# Modular_RFPA_v101.net
KiCad netlist of a schematic drawn in EAGLE
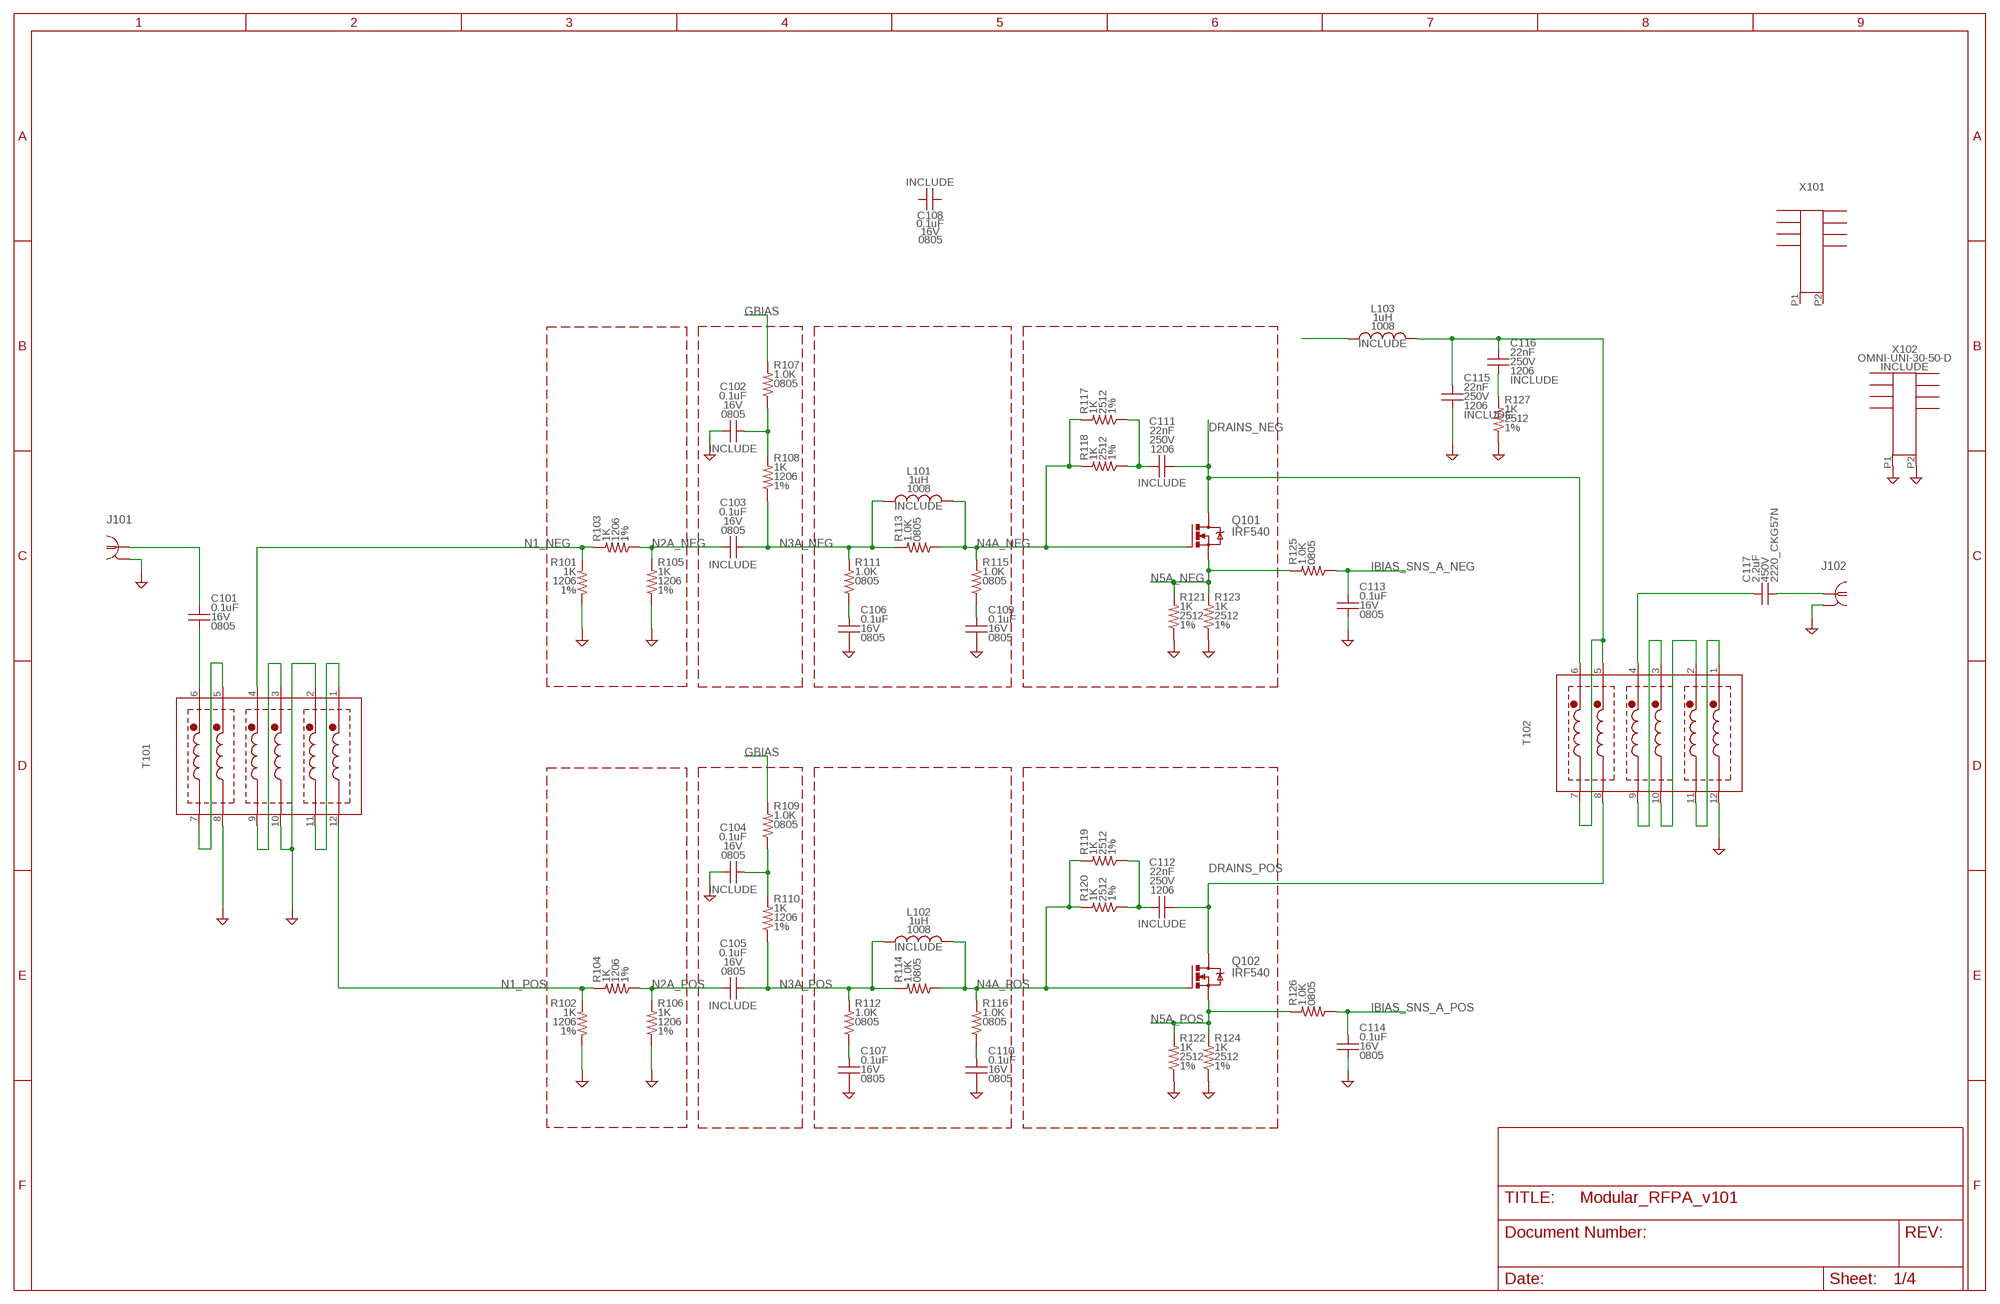
[diagram p0: schematic, sheet 1]
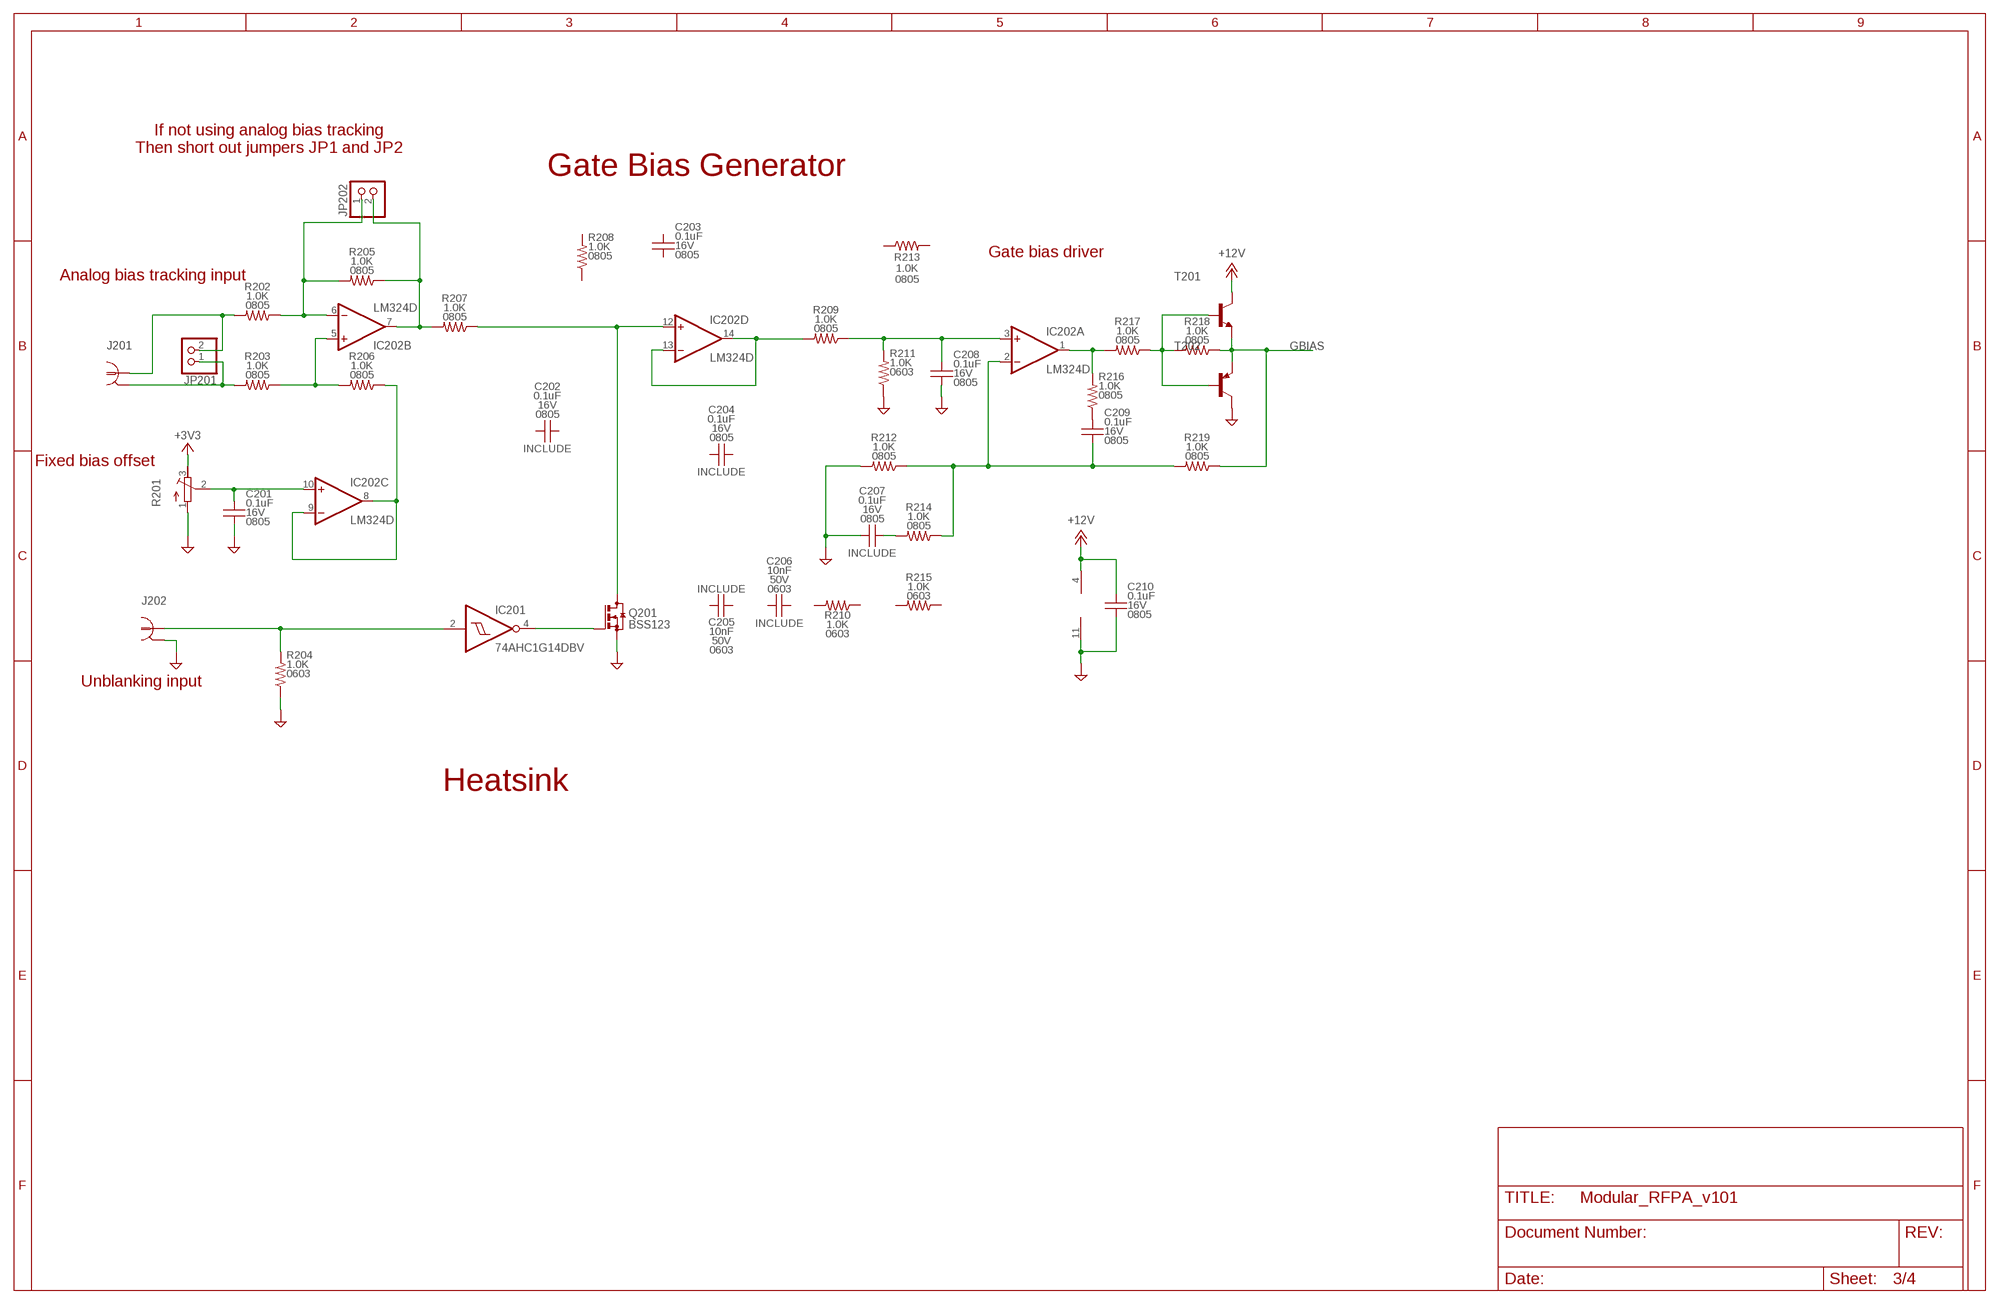
[diagram p1: schematic, sheet 3]
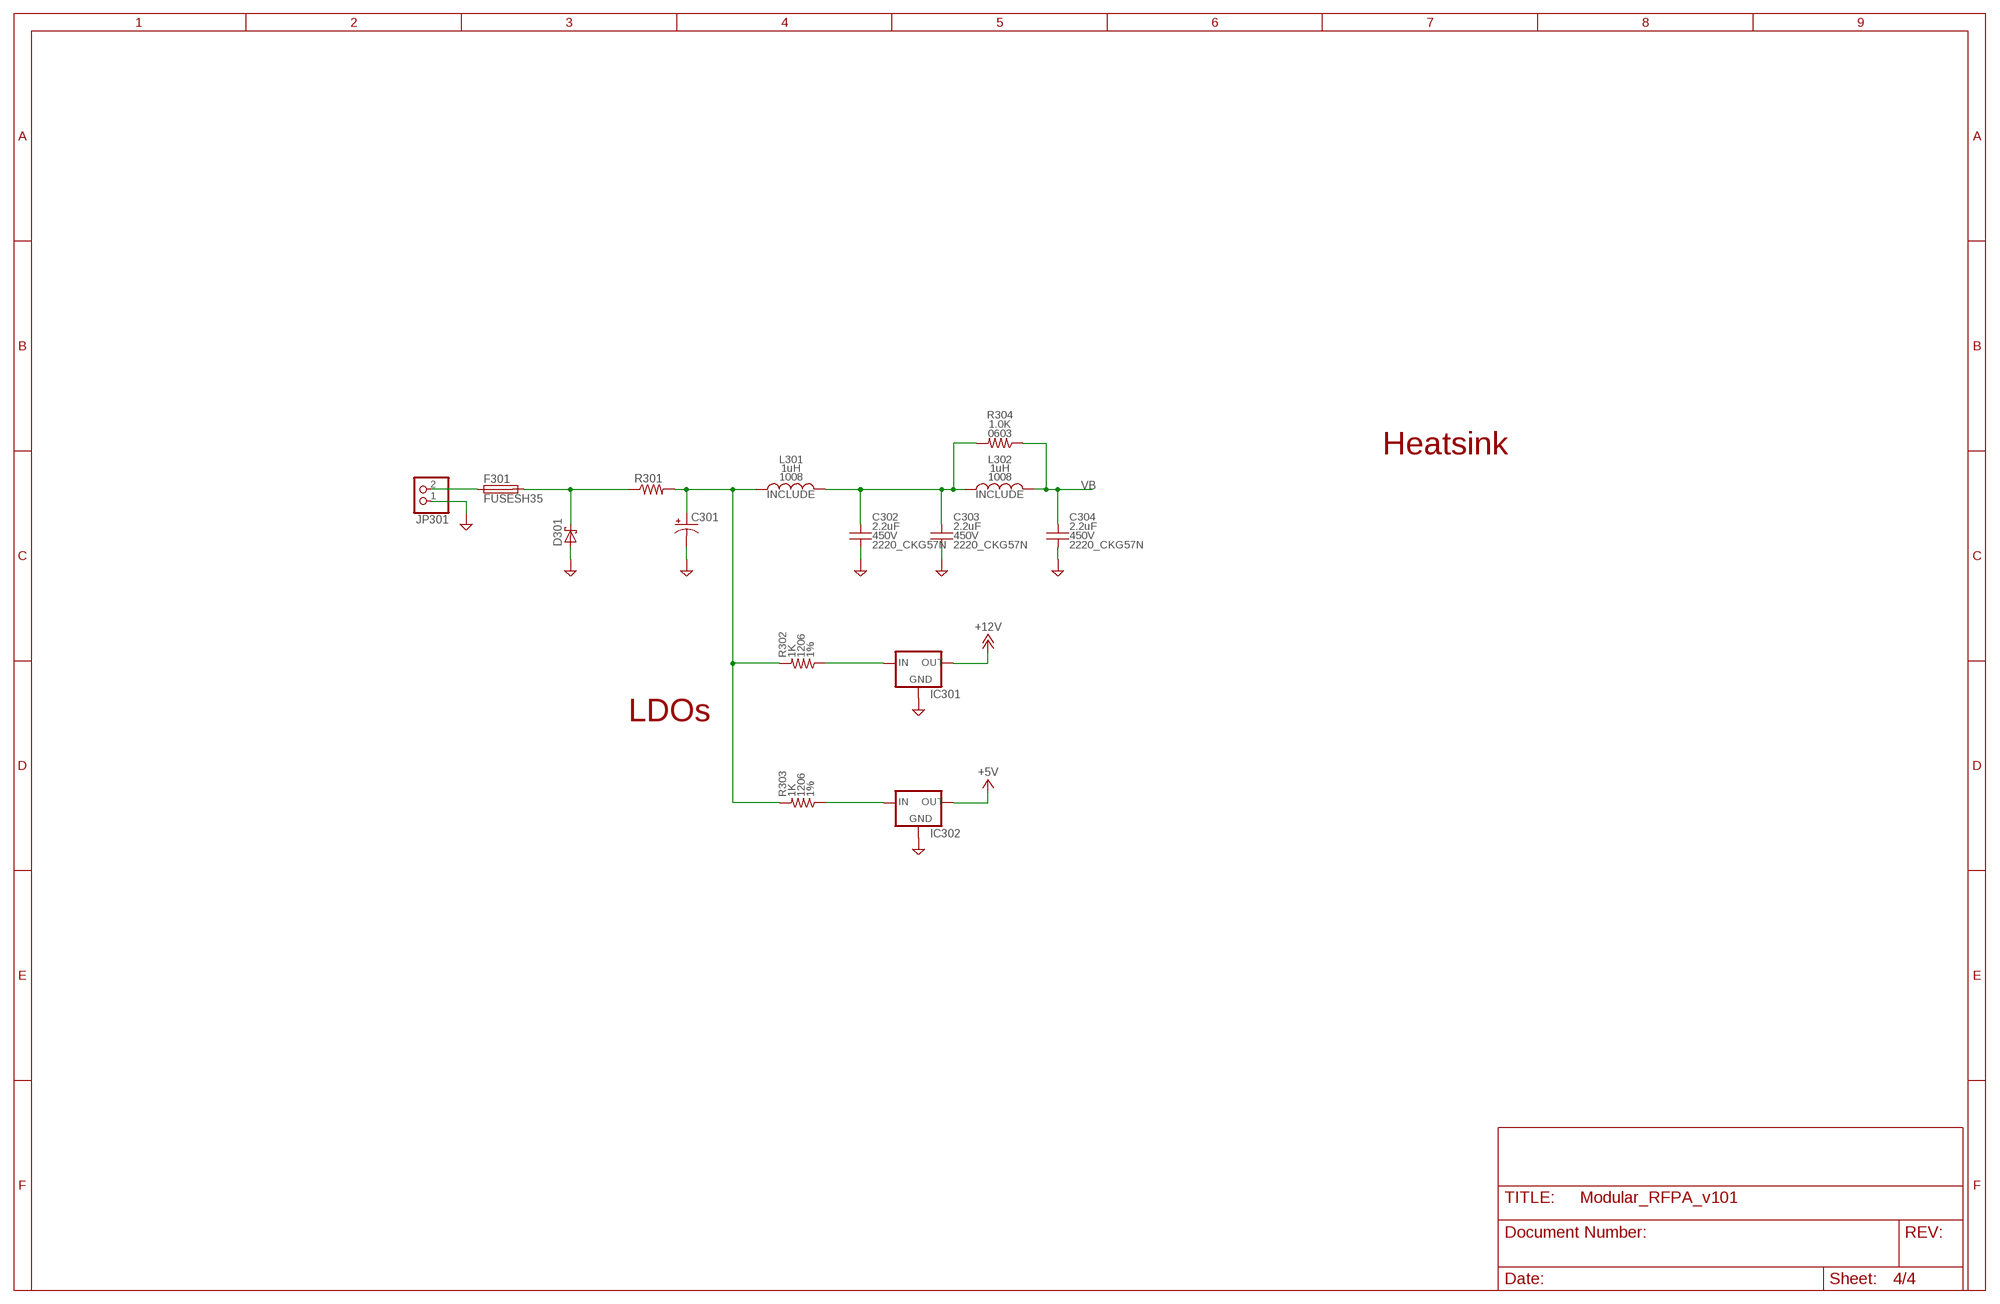
[diagram p2: schematic, sheet 4]

(export (version "E")
  (design (tool "Eeschema 10.0.6"))
  (components
    (comp (ref "C201")
      (value "0.1uF")
      (footprint "eagle-import:0805_IPC-7351B")
      (fields (field (name "VOLTAGE") "16V"))
      (libsource (lib "eagle-import") (part "C0805_IPCC-0.1U-16V-0805-X7R"))
    )
    (comp (ref "C202")
      (value "0.1uF")
      (footprint "eagle-import:0805_IPC-7351B")
      (fields (field (name "PACKAGE") "0805") (field (name "VOLTAGE") "16V") (field (name "BOM") "INCLUDE"))
      (libsource (lib "eagle-import") (part "C0805_IPCC-0.1U-16V-0805-X7R"))
    )
    (comp (ref "C203")
      (value "0.1uF")
      (footprint "eagle-import:0805_IPC-7351B")
      (fields (field (name "VOLTAGE") "16V"))
      (libsource (lib "eagle-import") (part "C0805_IPCC-0.1U-16V-0805-X7R"))
    )
    (comp (ref "C204")
      (value "0.1uF")
      (footprint "eagle-import:0805_IPC-7351B")
      (fields (field (name "PACKAGE") "0805") (field (name "VOLTAGE") "16V") (field (name "BOM") "INCLUDE"))
      (libsource (lib "eagle-import") (part "C0805_IPCC-0.1U-16V-0805-X7R"))
    )
    (comp (ref "C205")
      (value "10nF")
      (footprint "eagle-import:0603_IPC-7351B")
      (fields
        (field (name "BOM") "INCLUDE")
        (field (name "PACKAGE") "0603")
        (field (name "PARTNO") "C1608C0G1H103J080AA")
        (field (name "VOLTAGE") "50V")
      )
      (libsource (lib "eagle-import") (part "C0603_IPCC-10N-50V-0603-NP0"))
    )
    (comp (ref "C206")
      (value "10nF")
      (footprint "eagle-import:0603_IPC-7351B")
      (fields
        (field (name "BOM") "INCLUDE")
        (field (name "PACKAGE") "0603")
        (field (name "PARTNO") "C1608C0G1H103J080AA")
        (field (name "VOLTAGE") "50V")
      )
      (libsource (lib "eagle-import") (part "C0603_IPCC-10N-50V-0603-NP0"))
    )
    (comp (ref "C207")
      (value "0.1uF")
      (footprint "eagle-import:0805_IPC-7351B")
      (fields (field (name "PACKAGE") "0805") (field (name "VOLTAGE") "16V") (field (name "BOM") "INCLUDE"))
      (libsource (lib "eagle-import") (part "C0805_IPCC-0.1U-16V-0805-X7R"))
    )
    (comp (ref "C208")
      (value "0.1uF")
      (footprint "eagle-import:0805_IPC-7351B")
      (fields (field (name "VOLTAGE") "16V"))
      (libsource (lib "eagle-import") (part "C0805_IPCC-0.1U-16V-0805-X7R"))
    )
    (comp (ref "C209")
      (value "0.1uF")
      (footprint "eagle-import:0805_IPC-7351B")
      (fields (field (name "VOLTAGE") "16V"))
      (libsource (lib "eagle-import") (part "C0805_IPCC-0.1U-16V-0805-X7R"))
    )
    (comp (ref "C210")
      (value "0.1uF")
      (footprint "eagle-import:0805_IPC-7351B")
      (fields (field (name "VOLTAGE") "16V"))
      (libsource (lib "eagle-import") (part "C0805_IPCC-0.1U-16V-0805-X7R"))
    )
    (comp (ref "IC201")
      (value "74AHC1G14DBV")
      (footprint "eagle-import:SOT23-5")
      (libsource (lib "eagle-import") (part "741G14DBVAHC"))
    )
    (comp (ref "IC202")
      (value "LM324D")
      (footprint "eagle-import:SO14")
      (libsource (lib "eagle-import") (part "LM324D"))
    )
    (comp (ref "J201")
      (value "COAXBNC_EDGE")
      (footprint "eagle-import:BNC_EDGE")
      (libsource (lib "eagle-import") (part "COAXBNC_EDGE"))
    )
    (comp (ref "J202")
      (value "COAXBNC_EDGE")
      (footprint "eagle-import:BNC_EDGE")
      (libsource (lib "eagle-import") (part "COAXBNC_EDGE"))
    )
    (comp (ref "JP201")
      (value "PINHD-1X2")
      (footprint "eagle-import:1X02")
      (libsource (lib "eagle-import") (part "PINHD-1X2"))
    )
    (comp (ref "JP202")
      (value "PINHD-1X2")
      (footprint "eagle-import:1X02")
      (libsource (lib "eagle-import") (part "PINHD-1X2"))
    )
    (comp (ref "Q201")
      (value "BSS123")
      (footprint "eagle-import:SOT23")
      (libsource (lib "eagle-import") (part "BSS123"))
    )
    (comp (ref "R201")
      (value "R-TRIMM3299W")
      (footprint "eagle-import:RTRIM3299W")
      (libsource (lib "eagle-import") (part "R-TRIMM3299W"))
    )
    (comp (ref "R202")
      (value "1.0K")
      (footprint "eagle-import:0805_IPC-7351B")
      (fields (field (name "PACKAGE") "0805"))
      (libsource (lib "eagle-import") (part "R0805_IPCR-1.0K-0.1%-0805-0.1W"))
    )
    (comp (ref "R203")
      (value "1.0K")
      (footprint "eagle-import:0805_IPC-7351B")
      (fields (field (name "PACKAGE") "0805"))
      (libsource (lib "eagle-import") (part "R0805_IPCR-1.0K-0.1%-0805-0.1W"))
    )
    (comp (ref "R204")
      (value "1.0K")
      (footprint "eagle-import:0603_IPC-7351B")
      (libsource (lib "eagle-import") (part "R0603_IPCR-1.0K-0.1%-0603-0.1W"))
    )
    (comp (ref "R205")
      (value "1.0K")
      (footprint "eagle-import:0805_IPC-7351B")
      (fields (field (name "PACKAGE") "0805"))
      (libsource (lib "eagle-import") (part "R0805_IPCR-1.0K-0.1%-0805-0.1W"))
    )
    (comp (ref "R206")
      (value "1.0K")
      (footprint "eagle-import:0805_IPC-7351B")
      (fields (field (name "PACKAGE") "0805"))
      (libsource (lib "eagle-import") (part "R0805_IPCR-1.0K-0.1%-0805-0.1W"))
    )
    (comp (ref "R207")
      (value "1.0K")
      (footprint "eagle-import:0805_IPC-7351B")
      (fields (field (name "PACKAGE") "0805"))
      (libsource (lib "eagle-import") (part "R0805_IPCR-1.0K-0.1%-0805-0.1W"))
    )
    (comp (ref "R208")
      (value "1.0K")
      (footprint "eagle-import:0805_IPC-7351B")
      (libsource (lib "eagle-import") (part "R0805_IPCR-1.0K-0.1%-0805-0.1W"))
    )
    (comp (ref "R209")
      (value "1.0K")
      (footprint "eagle-import:0805_IPC-7351B")
      (fields (field (name "PACKAGE") "0805"))
      (libsource (lib "eagle-import") (part "R0805_IPCR-1.0K-0.1%-0805-0.1W"))
    )
    (comp (ref "R210")
      (value "1.0K")
      (footprint "eagle-import:0603_IPC-7351B")
      (fields (field (name "PACKAGE") "0603"))
      (libsource (lib "eagle-import") (part "R0603_IPCR-1.0K-0.1%-0603-0.1W"))
    )
    (comp (ref "R211")
      (value "1.0K")
      (footprint "eagle-import:0603_IPC-7351B")
      (libsource (lib "eagle-import") (part "R0603_IPCR-1.0K-0.1%-0603-0.1W"))
    )
    (comp (ref "R212")
      (value "1.0K")
      (footprint "eagle-import:0805_IPC-7351B")
      (fields (field (name "PACKAGE") "0805"))
      (libsource (lib "eagle-import") (part "R0805_IPCR-1.0K-0.1%-0805-0.1W"))
    )
    (comp (ref "R213")
      (value "1.0K")
      (footprint "eagle-import:0805_IPC-7351B")
      (fields (field (name "PACKAGE") "0805"))
      (libsource (lib "eagle-import") (part "R0805_IPCR-1.0K-0.1%-0805-0.1W"))
    )
    (comp (ref "R214")
      (value "1.0K")
      (footprint "eagle-import:0805_IPC-7351B")
      (fields (field (name "PACKAGE") "0805"))
      (libsource (lib "eagle-import") (part "R0805_IPCR-1.0K-0.1%-0805-0.1W"))
    )
    (comp (ref "R215")
      (value "1.0K")
      (footprint "eagle-import:0603_IPC-7351B")
      (fields (field (name "PACKAGE") "0603"))
      (libsource (lib "eagle-import") (part "R0603_IPCR-1.0K-0.1%-0603-0.1W"))
    )
    (comp (ref "R216")
      (value "1.0K")
      (footprint "eagle-import:0805_IPC-7351B")
      (libsource (lib "eagle-import") (part "R0805_IPCR-1.0K-0.1%-0805-0.1W"))
    )
    (comp (ref "R217")
      (value "1.0K")
      (footprint "eagle-import:0805_IPC-7351B")
      (fields (field (name "PACKAGE") "0805"))
      (libsource (lib "eagle-import") (part "R0805_IPCR-1.0K-0.1%-0805-0.1W"))
    )
    (comp (ref "R218")
      (value "1.0K")
      (footprint "eagle-import:0805_IPC-7351B")
      (fields (field (name "PACKAGE") "0805"))
      (libsource (lib "eagle-import") (part "R0805_IPCR-1.0K-0.1%-0805-0.1W"))
    )
    (comp (ref "R219")
      (value "1.0K")
      (footprint "eagle-import:0805_IPC-7351B")
      (fields (field (name "PACKAGE") "0805"))
      (libsource (lib "eagle-import") (part "R0805_IPCR-1.0K-0.1%-0805-0.1W"))
    )
    (comp (ref "T201")
      (value "BC808-NPN-SOT23-BEC")
      (footprint "eagle-import:SOT23-BEC")
      (libsource (lib "eagle-import") (part "-NPN-SOT23-BECBC808"))
    )
    (comp (ref "T202")
      (value "BC807-16-PNP-SOT23-BEC")
      (footprint "eagle-import:SOT23-BEC")
      (libsource (lib "eagle-import") (part "-PNP-SOT23-BECBC807-16"))
    )
    (comp (ref "C301")
      (value "CPOL-USE10-25")
      (footprint "eagle-import:EB25D")
      (libsource (lib "eagle-import") (part "CPOL-USE10-25"))
    )
    (comp (ref "C302")
      (value "2.2uF")
      (footprint "eagle-import:C2220_CKG57N")
      (fields (field (name "PARTNO") "CKG57NX7T2W225M500JJ") (field (name "VOLTAGE") "450V"))
      (libsource (lib "eagle-import") (part "CC2220_CKG57NC-2.2U-450V-20%-2220-X7T"))
    )
    (comp (ref "C303")
      (value "2.2uF")
      (footprint "eagle-import:C2220_CKG57N")
      (fields (field (name "PARTNO") "CKG57NX7T2W225M500JJ") (field (name "VOLTAGE") "450V"))
      (libsource (lib "eagle-import") (part "CC2220_CKG57NC-2.2U-450V-20%-2220-X7T"))
    )
    (comp (ref "C304")
      (value "2.2uF")
      (footprint "eagle-import:C2220_CKG57N")
      (fields (field (name "PARTNO") "CKG57NX7T2W225M500JJ") (field (name "VOLTAGE") "450V"))
      (libsource (lib "eagle-import") (part "CC2220_CKG57NC-2.2U-450V-20%-2220-X7T"))
    )
    (comp (ref "D301")
      (value "SCHOTTKY-DIODESMC")
      (footprint "eagle-import:SMC")
      (libsource (lib "eagle-import") (part "SCHOTTKY-DIODESMC"))
    )
    (comp (ref "F301")
      (value "FUSESH35")
      (footprint "eagle-import:SH25")
      (libsource (lib "eagle-import") (part "FUSESH35"))
    )
    (comp (ref "IC301")
      (value "78XXS")
      (footprint "eagle-import:78XXS")
      (libsource (lib "eagle-import") (part "78XXS"))
    )
    (comp (ref "IC302")
      (value "78XXS")
      (footprint "eagle-import:78XXS")
      (libsource (lib "eagle-import") (part "78XXS"))
    )
    (comp (ref "JP301")
      (value "PINHD-1X2")
      (footprint "eagle-import:1X02")
      (libsource (lib "eagle-import") (part "PINHD-1X2"))
    )
    (comp (ref "L301")
      (value "1uH")
      (footprint "eagle-import:L1008")
      (fields (field (name "PARTNO") "1008CS-102XJEC"))
      (libsource (lib "eagle-import") (part "L_CHIP1008L-1.0U-AIR-5%-1008-0.37A"))
    )
    (comp (ref "L302")
      (value "1uH")
      (footprint "eagle-import:L1008")
      (fields (field (name "PARTNO") "1008CS-102XJEC"))
      (libsource (lib "eagle-import") (part "L_CHIP1008L-1.0U-AIR-5%-1008-0.37A"))
    )
    (comp (ref "R301")
      (value "R-US_0617/22")
      (footprint "eagle-import:0617_22")
      (libsource (lib "eagle-import") (part "R-US_0617/22"))
    )
    (comp (ref "R302")
      (value "1K")
      (footprint "eagle-import:R1206")
      (fields (field (name "POWER") "0.25"))
      (libsource (lib "eagle-import") (part "RR1206R-1.0K-1%-1206-0.25W"))
    )
    (comp (ref "R303")
      (value "1K")
      (footprint "eagle-import:R1206")
      (fields (field (name "POWER") "0.25"))
      (libsource (lib "eagle-import") (part "RR1206R-1.0K-1%-1206-0.25W"))
    )
    (comp (ref "R304")
      (value "1.0K")
      (footprint "eagle-import:0603_IPC-7351B")
      (fields (field (name "PACKAGE") "0603"))
      (libsource (lib "eagle-import") (part "R0603_IPCR-1.0K-0.1%-0603-0.1W"))
    )
    (comp (ref "C101")
      (value "0.1uF")
      (footprint "eagle-import:0805_IPC-7351B")
      (fields (field (name "VOLTAGE") "16V"))
      (libsource (lib "eagle-import") (part "C0805_IPCC-0.1U-16V-0805-X7R"))
    )
    (comp (ref "C102")
      (value "0.1uF")
      (footprint "eagle-import:0805_IPC-7351B")
      (fields (field (name "PACKAGE") "0805") (field (name "VOLTAGE") "16V") (field (name "BOM") "INCLUDE"))
      (libsource (lib "eagle-import") (part "C0805_IPCC-0.1U-16V-0805-X7R"))
    )
    (comp (ref "C103")
      (value "0.1uF")
      (footprint "eagle-import:0805_IPC-7351B")
      (fields (field (name "PACKAGE") "0805") (field (name "VOLTAGE") "16V") (field (name "BOM") "INCLUDE"))
      (libsource (lib "eagle-import") (part "C0805_IPCC-0.1U-16V-0805-X7R"))
    )
    (comp (ref "C104")
      (value "0.1uF")
      (footprint "eagle-import:0805_IPC-7351B")
      (fields (field (name "PACKAGE") "0805") (field (name "VOLTAGE") "16V") (field (name "BOM") "INCLUDE"))
      (libsource (lib "eagle-import") (part "C0805_IPCC-0.1U-16V-0805-X7R"))
    )
    (comp (ref "C105")
      (value "0.1uF")
      (footprint "eagle-import:0805_IPC-7351B")
      (fields (field (name "PACKAGE") "0805") (field (name "VOLTAGE") "16V") (field (name "BOM") "INCLUDE"))
      (libsource (lib "eagle-import") (part "C0805_IPCC-0.1U-16V-0805-X7R"))
    )
    (comp (ref "C106")
      (value "0.1uF")
      (footprint "eagle-import:0805_IPC-7351B")
      (fields (field (name "VOLTAGE") "16V"))
      (libsource (lib "eagle-import") (part "C0805_IPCC-0.1U-16V-0805-X7R"))
    )
    (comp (ref "C107")
      (value "0.1uF")
      (footprint "eagle-import:0805_IPC-7351B")
      (fields (field (name "VOLTAGE") "16V"))
      (libsource (lib "eagle-import") (part "C0805_IPCC-0.1U-16V-0805-X7R"))
    )
    (comp (ref "C108")
      (value "0.1uF")
      (footprint "eagle-import:0805_IPC-7351B")
      (fields (field (name "PACKAGE") "0805") (field (name "VOLTAGE") "16V") (field (name "BOM") "INCLUDE"))
      (libsource (lib "eagle-import") (part "C0805_IPCC-0.1U-16V-0805-X7R"))
    )
    (comp (ref "C109")
      (value "0.1uF")
      (footprint "eagle-import:0805_IPC-7351B")
      (fields (field (name "VOLTAGE") "16V"))
      (libsource (lib "eagle-import") (part "C0805_IPCC-0.1U-16V-0805-X7R"))
    )
    (comp (ref "C110")
      (value "0.1uF")
      (footprint "eagle-import:0805_IPC-7351B")
      (fields (field (name "VOLTAGE") "16V"))
      (libsource (lib "eagle-import") (part "C0805_IPCC-0.1U-16V-0805-X7R"))
    )
    (comp (ref "C111")
      (value "22nF")
      (footprint "eagle-import:C1206")
      (fields
        (field (name "BOM") "INCLUDE")
        (field (name "PACKAGE") "1206")
        (field (name "PARTNO") "C3216NP02E223J160AA")
        (field (name "VOLTAGE") "250V")
      )
      (libsource (lib "eagle-import") (part "CC1206C-22N-250V-5%-1206-NP0"))
    )
    (comp (ref "C112")
      (value "22nF")
      (footprint "eagle-import:C1206")
      (fields
        (field (name "BOM") "INCLUDE")
        (field (name "PACKAGE") "1206")
        (field (name "PARTNO") "C3216NP02E223J160AA")
        (field (name "VOLTAGE") "250V")
      )
      (libsource (lib "eagle-import") (part "CC1206C-22N-250V-5%-1206-NP0"))
    )
    (comp (ref "C113")
      (value "0.1uF")
      (footprint "eagle-import:0805_IPC-7351B")
      (fields (field (name "VOLTAGE") "16V"))
      (libsource (lib "eagle-import") (part "C0805_IPCC-0.1U-16V-0805-X7R"))
    )
    (comp (ref "C114")
      (value "0.1uF")
      (footprint "eagle-import:0805_IPC-7351B")
      (fields (field (name "VOLTAGE") "16V"))
      (libsource (lib "eagle-import") (part "C0805_IPCC-0.1U-16V-0805-X7R"))
    )
    (comp (ref "C115")
      (value "22nF")
      (footprint "eagle-import:C1206")
      (fields (field (name "PARTNO") "C3216NP02E223J160AA") (field (name "VOLTAGE") "250V"))
      (libsource (lib "eagle-import") (part "CC1206C-22N-250V-5%-1206-NP0"))
    )
    (comp (ref "C116")
      (value "22nF")
      (footprint "eagle-import:C1206")
      (fields (field (name "PARTNO") "C3216NP02E223J160AA") (field (name "VOLTAGE") "250V"))
      (libsource (lib "eagle-import") (part "CC1206C-22N-250V-5%-1206-NP0"))
    )
    (comp (ref "C117")
      (value "2.2uF")
      (footprint "eagle-import:C2220_CKG57N")
      (fields (field (name "PARTNO") "CKG57NX7T2W225M500JJ") (field (name "VOLTAGE") "450V"))
      (libsource (lib "eagle-import") (part "CC2220_CKG57NC-2.2U-450V-20%-2220-X7T"))
    )
    (comp (ref "J101")
      (value "COAXBNC_EDGE")
      (footprint "eagle-import:BNC_EDGE")
      (libsource (lib "eagle-import") (part "COAXBNC_EDGE"))
    )
    (comp (ref "J102")
      (value "COAXBNC_EDGE")
      (footprint "eagle-import:BNC_EDGE")
      (libsource (lib "eagle-import") (part "COAXBNC_EDGE"))
    )
    (comp (ref "L101")
      (value "1uH")
      (footprint "eagle-import:L1008")
      (fields (field (name "PARTNO") "1008CS-102XJEC"))
      (libsource (lib "eagle-import") (part "L_CHIP1008L-1.0U-AIR-5%-1008-0.37A"))
    )
    (comp (ref "L102")
      (value "1uH")
      (footprint "eagle-import:L1008")
      (fields (field (name "PARTNO") "1008CS-102XJEC"))
      (libsource (lib "eagle-import") (part "L_CHIP1008L-1.0U-AIR-5%-1008-0.37A"))
    )
    (comp (ref "L103")
      (value "1uH")
      (footprint "eagle-import:L1008")
      (fields (field (name "PARTNO") "1008CS-102XJEC"))
      (libsource (lib "eagle-import") (part "L_CHIP1008L-1.0U-AIR-5%-1008-0.37A"))
    )
    (comp (ref "Q101")
      (value "IRF540")
      (footprint "eagle-import:TO220BV")
      (libsource (lib "eagle-import") (part "IRF540"))
    )
    (comp (ref "Q102")
      (value "IRF540")
      (footprint "eagle-import:TO220BV")
      (libsource (lib "eagle-import") (part "IRF540"))
    )
    (comp (ref "R101")
      (value "1K")
      (footprint "eagle-import:R1206")
      (fields (field (name "POWER") "0.25"))
      (libsource (lib "eagle-import") (part "RR1206R-1.0K-1%-1206-0.25W"))
    )
    (comp (ref "R102")
      (value "1K")
      (footprint "eagle-import:R1206")
      (fields (field (name "POWER") "0.25"))
      (libsource (lib "eagle-import") (part "RR1206R-1.0K-1%-1206-0.25W"))
    )
    (comp (ref "R103")
      (value "1K")
      (footprint "eagle-import:R1206")
      (fields (field (name "POWER") "0.25"))
      (libsource (lib "eagle-import") (part "RR1206R-1.0K-1%-1206-0.25W"))
    )
    (comp (ref "R104")
      (value "1K")
      (footprint "eagle-import:R1206")
      (fields (field (name "POWER") "0.25"))
      (libsource (lib "eagle-import") (part "RR1206R-1.0K-1%-1206-0.25W"))
    )
    (comp (ref "R105")
      (value "1K")
      (footprint "eagle-import:R1206")
      (fields (field (name "POWER") "0.25"))
      (libsource (lib "eagle-import") (part "RR1206R-1.0K-1%-1206-0.25W"))
    )
    (comp (ref "R106")
      (value "1K")
      (footprint "eagle-import:R1206")
      (fields (field (name "POWER") "0.25"))
      (libsource (lib "eagle-import") (part "RR1206R-1.0K-1%-1206-0.25W"))
    )
    (comp (ref "R107")
      (value "1.0K")
      (footprint "eagle-import:0805_IPC-7351B")
      (libsource (lib "eagle-import") (part "R0805_IPCR-1.0K-0.1%-0805-0.1W"))
    )
    (comp (ref "R108")
      (value "1K")
      (footprint "eagle-import:R1206")
      (fields (field (name "POWER") "0.25"))
      (libsource (lib "eagle-import") (part "RR1206R-1.0K-1%-1206-0.25W"))
    )
    (comp (ref "R109")
      (value "1.0K")
      (footprint "eagle-import:0805_IPC-7351B")
      (libsource (lib "eagle-import") (part "R0805_IPCR-1.0K-0.1%-0805-0.1W"))
    )
    (comp (ref "R110")
      (value "1K")
      (footprint "eagle-import:R1206")
      (fields (field (name "POWER") "0.25"))
      (libsource (lib "eagle-import") (part "RR1206R-1.0K-1%-1206-0.25W"))
    )
    (comp (ref "R111")
      (value "1.0K")
      (footprint "eagle-import:0805_IPC-7351B")
      (libsource (lib "eagle-import") (part "R0805_IPCR-1.0K-0.1%-0805-0.1W"))
    )
    (comp (ref "R112")
      (value "1.0K")
      (footprint "eagle-import:0805_IPC-7351B")
      (libsource (lib "eagle-import") (part "R0805_IPCR-1.0K-0.1%-0805-0.1W"))
    )
    (comp (ref "R113")
      (value "1.0K")
      (footprint "eagle-import:0805_IPC-7351B")
      (libsource (lib "eagle-import") (part "R0805_IPCR-1.0K-0.1%-0805-0.1W"))
    )
    (comp (ref "R114")
      (value "1.0K")
      (footprint "eagle-import:0805_IPC-7351B")
      (libsource (lib "eagle-import") (part "R0805_IPCR-1.0K-0.1%-0805-0.1W"))
    )
    (comp (ref "R115")
      (value "1.0K")
      (footprint "eagle-import:0805_IPC-7351B")
      (libsource (lib "eagle-import") (part "R0805_IPCR-1.0K-0.1%-0805-0.1W"))
    )
    (comp (ref "R116")
      (value "1.0K")
      (footprint "eagle-import:0805_IPC-7351B")
      (libsource (lib "eagle-import") (part "R0805_IPCR-1.0K-0.1%-0805-0.1W"))
    )
    (comp (ref "R117")
      (value "1K")
      (footprint "eagle-import:R2512")
      (fields (field (name "POWER") "1"))
      (libsource (lib "eagle-import") (part "RR2512R-1K-1%-2512-1W"))
    )
    (comp (ref "R118")
      (value "1K")
      (footprint "eagle-import:R2512")
      (fields (field (name "POWER") "1"))
      (libsource (lib "eagle-import") (part "RR2512R-1K-1%-2512-1W"))
    )
    (comp (ref "R119")
      (value "1K")
      (footprint "eagle-import:R2512")
      (fields (field (name "POWER") "1"))
      (libsource (lib "eagle-import") (part "RR2512R-1K-1%-2512-1W"))
    )
    (comp (ref "R120")
      (value "1K")
      (footprint "eagle-import:R2512")
      (fields (field (name "POWER") "1"))
      (libsource (lib "eagle-import") (part "RR2512R-1K-1%-2512-1W"))
    )
    (comp (ref "R121")
      (value "1K")
      (footprint "eagle-import:R2512")
      (fields (field (name "POWER") "1"))
      (libsource (lib "eagle-import") (part "RR2512R-1K-1%-2512-1W"))
    )
    (comp (ref "R122")
      (value "1K")
      (footprint "eagle-import:R2512")
      (fields (field (name "POWER") "1"))
      (libsource (lib "eagle-import") (part "RR2512R-1K-1%-2512-1W"))
    )
    (comp (ref "R123")
      (value "1K")
      (footprint "eagle-import:R2512")
      (fields (field (name "POWER") "1"))
      (libsource (lib "eagle-import") (part "RR2512R-1K-1%-2512-1W"))
    )
    (comp (ref "R124")
      (value "1K")
      (footprint "eagle-import:R2512")
      (fields (field (name "POWER") "1"))
      (libsource (lib "eagle-import") (part "RR2512R-1K-1%-2512-1W"))
    )
    (comp (ref "R125")
      (value "1.0K")
      (footprint "eagle-import:0805_IPC-7351B")
      (libsource (lib "eagle-import") (part "R0805_IPCR-1.0K-0.1%-0805-0.1W"))
    )
    (comp (ref "R126")
      (value "1.0K")
      (footprint "eagle-import:0805_IPC-7351B")
      (libsource (lib "eagle-import") (part "R0805_IPCR-1.0K-0.1%-0805-0.1W"))
    )
    (comp (ref "R127")
      (value "1K")
      (footprint "eagle-import:R2512")
      (fields (field (name "POWER") "1"))
      (libsource (lib "eagle-import") (part "RR2512R-1K-1%-2512-1W"))
    )
    (comp (ref "T101")
      (value "HP5_TRAFOHP5")
      (footprint "eagle-import:HP5")
      (libsource (lib "eagle-import") (part "HP5_TRAFOHP5"))
    )
    (comp (ref "T102")
      (value "HP5_TRAFOHP5")
      (footprint "eagle-import:HP5")
      (libsource (lib "eagle-import") (part "HP5_TRAFOHP5"))
    )
    (comp (ref "X101")
      (value "HEATSINK_OMNI_DUAL30-75-D")
      (footprint "eagle-import:OMNI-UNI-30-75-D")
      (libsource (lib "eagle-import") (part "HEATSINK_OMNI_DUAL30-75-D"))
    )
    (comp (ref "X102")
      (value "HEATSINK_OMNI_DUALOMNI-UNI-30-50-DUNI-30-50-D")
      (footprint "eagle-import:OMNI-UNI-30-50-D")
      (fields (field (name "PARTNO") "OMNI-UNI-30-50-D"))
      (libsource (lib "eagle-import") (part "HEATSINK_OMNI_DUALUNI-30-50-DOMNI-UNI-30-50-D"))
    )
  )
  (nets
    (net (code "1") (name "+3V3") (class "Default")
      (node (ref "R201") (pin "3") (pinfunction "E_3") (pintype "passive"))
    )
    (net (code "2") (name "+5V") (class "Default")
      (node (ref "IC302") (pin "OUT") (pinfunction "OUT_OUT") (pintype "passive"))
    )
    (net (code "3") (name "+12V") (class "Default")
      (node (ref "C210") (pin "1") (pinfunction "1_1") (pintype "passive"))
      (node (ref "IC202") (pin "4") (pinfunction "V+_4") (pintype "power_in"))
      (node (ref "IC301") (pin "OUT") (pinfunction "OUT_OUT") (pintype "passive"))
      (node (ref "T201") (pin "C") (pinfunction "C_C") (pintype "passive"))
    )
    (net (code "4") (name "DRAINS_NEG") (class "Default")
      (node (ref "C111") (pin "2") (pinfunction "2_2") (pintype "passive"))
      (node (ref "Q101") (pin "D") (pinfunction "D_D") (pintype "passive"))
      (node (ref "T102") (pin "6") (pinfunction "S6_6") (pintype "passive"))
    )
    (net (code "5") (name "DRAINS_POS") (class "Default")
      (node (ref "C112") (pin "2") (pinfunction "2_2") (pintype "passive"))
      (node (ref "Q102") (pin "D") (pinfunction "D_D") (pintype "passive"))
      (node (ref "T102") (pin "8") (pinfunction "F5_8") (pintype "passive"))
    )
    (net (code "6") (name "GBIAS") (class "Default")
      (node (ref "R107") (pin "1") (pinfunction "1_1") (pintype "passive"))
      (node (ref "R109") (pin "1") (pinfunction "1_1") (pintype "passive"))
      (node (ref "R218") (pin "2") (pinfunction "2_2") (pintype "passive"))
      (node (ref "R219") (pin "2") (pinfunction "2_2") (pintype "passive"))
      (node (ref "T201") (pin "E") (pinfunction "E_E") (pintype "passive"))
      (node (ref "T202") (pin "E") (pinfunction "E_E") (pintype "passive"))
    )
    (net (code "7") (name "GND") (class "Default")
      (node (ref "C102") (pin "2") (pinfunction "2_2") (pintype "passive"))
      (node (ref "C104") (pin "2") (pinfunction "2_2") (pintype "passive"))
      (node (ref "C106") (pin "2") (pinfunction "2_2") (pintype "passive"))
      (node (ref "C107") (pin "2") (pinfunction "2_2") (pintype "passive"))
      (node (ref "C109") (pin "2") (pinfunction "2_2") (pintype "passive"))
      (node (ref "C110") (pin "2") (pinfunction "2_2") (pintype "passive"))
      (node (ref "C113") (pin "2") (pinfunction "2_2") (pintype "passive"))
      (node (ref "C114") (pin "2") (pinfunction "2_2") (pintype "passive"))
      (node (ref "C115") (pin "2") (pinfunction "2_2") (pintype "passive"))
      (node (ref "C201") (pin "2") (pinfunction "2_2") (pintype "passive"))
      (node (ref "C207") (pin "2") (pinfunction "2_2") (pintype "passive"))
      (node (ref "C208") (pin "2") (pinfunction "2_2") (pintype "passive"))
      (node (ref "C210") (pin "2") (pinfunction "2_2") (pintype "passive"))
      (node (ref "C301") (pin "-") (pinfunction "-_-") (pintype "passive"))
      (node (ref "C302") (pin "2") (pinfunction "2_2") (pintype "passive"))
      (node (ref "C303") (pin "2") (pinfunction "2_2") (pintype "passive"))
      (node (ref "C304") (pin "2") (pinfunction "2_2") (pintype "passive"))
      (node (ref "D301") (pin "A") (pinfunction "A_A") (pintype "passive"))
      (node (ref "IC202") (pin "11") (pinfunction "V-_11") (pintype "power_in"))
      (node (ref "IC301") (pin "GND") (pinfunction "GND_GND") (pintype "input"))
      (node (ref "IC302") (pin "GND") (pinfunction "GND_GND") (pintype "input"))
      (node (ref "J101") (pin "G1") (pinfunction "GND1_G1") (pintype "power_in"))
      (node (ref "J101") (pin "G2") (pinfunction "GND1_G2") (pintype "power_in"))
      (node (ref "J101") (pin "G3") (pinfunction "GND1_G3") (pintype "power_in"))
      (node (ref "J101") (pin "G4") (pinfunction "GND1_G4") (pintype "power_in"))
      (node (ref "J102") (pin "G1") (pinfunction "GND1_G1") (pintype "power_in"))
      (node (ref "J102") (pin "G2") (pinfunction "GND1_G2") (pintype "power_in"))
      (node (ref "J102") (pin "G3") (pinfunction "GND1_G3") (pintype "power_in"))
      (node (ref "J102") (pin "G4") (pinfunction "GND1_G4") (pintype "power_in"))
      (node (ref "J202") (pin "G1") (pinfunction "GND1_G1") (pintype "power_in"))
      (node (ref "J202") (pin "G2") (pinfunction "GND1_G2") (pintype "power_in"))
      (node (ref "J202") (pin "G3") (pinfunction "GND1_G3") (pintype "power_in"))
      (node (ref "J202") (pin "G4") (pinfunction "GND1_G4") (pintype "power_in"))
      (node (ref "JP301") (pin "1") (pinfunction "1_1") (pintype "passive"))
      (node (ref "Q201") (pin "2") (pinfunction "S_2") (pintype "passive"))
      (node (ref "R101") (pin "2") (pinfunction "2_2") (pintype "passive"))
      (node (ref "R102") (pin "2") (pinfunction "2_2") (pintype "passive"))
      (node (ref "R105") (pin "2") (pinfunction "2_2") (pintype "passive"))
      (node (ref "R106") (pin "2") (pinfunction "2_2") (pintype "passive"))
      (node (ref "R121") (pin "2") (pinfunction "2_2") (pintype "passive"))
      (node (ref "R122") (pin "2") (pinfunction "2_2") (pintype "passive"))
      (node (ref "R123") (pin "2") (pinfunction "2_2") (pintype "passive"))
      (node (ref "R124") (pin "2") (pinfunction "2_2") (pintype "passive"))
      (node (ref "R127") (pin "2") (pinfunction "2_2") (pintype "passive"))
      (node (ref "R201") (pin "1") (pinfunction "A_1") (pintype "passive"))
      (node (ref "R204") (pin "2") (pinfunction "2_2") (pintype "passive"))
      (node (ref "R211") (pin "2") (pinfunction "2_2") (pintype "passive"))
      (node (ref "R212") (pin "1") (pinfunction "1_1") (pintype "passive"))
      (node (ref "T101") (pin "10") (pinfunction "F3_10") (pintype "passive"))
      (node (ref "T101") (pin "2") (pinfunction "S2_2") (pintype "passive"))
      (node (ref "T101") (pin "8") (pinfunction "F5_8") (pintype "passive"))
      (node (ref "T102") (pin "12") (pinfunction "F1_12") (pintype "passive"))
      (node (ref "T202") (pin "C") (pinfunction "C_C") (pintype "passive"))
      (node (ref "X102") (pin "P1") (pinfunction "P$1_P1") (pintype "bidirectional"))
      (node (ref "X102") (pin "P2") (pinfunction "P$2_P2") (pintype "bidirectional"))
    )
    (net (code "8") (name "IBIAS_SNS_A_NEG") (class "Default")
      (node (ref "C113") (pin "1") (pinfunction "1_1") (pintype "passive"))
      (node (ref "R125") (pin "2") (pinfunction "2_2") (pintype "passive"))
    )
    (net (code "9") (name "IBIAS_SNS_A_POS") (class "Default")
      (node (ref "C114") (pin "1") (pinfunction "1_1") (pintype "passive"))
      (node (ref "R126") (pin "2") (pinfunction "2_2") (pintype "passive"))
    )
    (net (code "10") (name "N1_NEG") (class "Default")
      (node (ref "R101") (pin "1") (pinfunction "1_1") (pintype "passive"))
      (node (ref "R103") (pin "1") (pinfunction "1_1") (pintype "passive"))
      (node (ref "T101") (pin "4") (pinfunction "S4_4") (pintype "passive"))
    )
    (net (code "11") (name "N1_POS") (class "Default")
      (node (ref "R102") (pin "1") (pinfunction "1_1") (pintype "passive"))
      (node (ref "R104") (pin "1") (pinfunction "1_1") (pintype "passive"))
      (node (ref "T101") (pin "12") (pinfunction "F1_12") (pintype "passive"))
    )
    (net (code "12") (name "N2A_NEG") (class "Default")
      (node (ref "C103") (pin "2") (pinfunction "2_2") (pintype "passive"))
      (node (ref "R103") (pin "2") (pinfunction "2_2") (pintype "passive"))
      (node (ref "R105") (pin "1") (pinfunction "1_1") (pintype "passive"))
    )
    (net (code "13") (name "N2A_POS") (class "Default")
      (node (ref "C105") (pin "2") (pinfunction "2_2") (pintype "passive"))
      (node (ref "R104") (pin "2") (pinfunction "2_2") (pintype "passive"))
      (node (ref "R106") (pin "1") (pinfunction "1_1") (pintype "passive"))
    )
    (net (code "14") (name "N3A_NEG") (class "Default")
      (node (ref "C103") (pin "1") (pinfunction "1_1") (pintype "passive"))
      (node (ref "L101") (pin "1") (pinfunction "1_1") (pintype "passive"))
      (node (ref "R108") (pin "2") (pinfunction "2_2") (pintype "passive"))
      (node (ref "R111") (pin "1") (pinfunction "1_1") (pintype "passive"))
      (node (ref "R113") (pin "1") (pinfunction "1_1") (pintype "passive"))
    )
    (net (code "15") (name "N3A_POS") (class "Default")
      (node (ref "C105") (pin "1") (pinfunction "1_1") (pintype "passive"))
      (node (ref "L102") (pin "1") (pinfunction "1_1") (pintype "passive"))
      (node (ref "R110") (pin "2") (pinfunction "2_2") (pintype "passive"))
      (node (ref "R112") (pin "1") (pinfunction "1_1") (pintype "passive"))
      (node (ref "R114") (pin "1") (pinfunction "1_1") (pintype "passive"))
    )
    (net (code "16") (name "N4A_NEG") (class "Default")
      (node (ref "L101") (pin "2") (pinfunction "2_2") (pintype "passive"))
      (node (ref "Q101") (pin "G") (pinfunction "G_G") (pintype "passive"))
      (node (ref "R113") (pin "2") (pinfunction "2_2") (pintype "passive"))
      (node (ref "R115") (pin "1") (pinfunction "1_1") (pintype "passive"))
      (node (ref "R117") (pin "1") (pinfunction "1_1") (pintype "passive"))
      (node (ref "R118") (pin "1") (pinfunction "1_1") (pintype "passive"))
    )
    (net (code "17") (name "N4A_POS") (class "Default")
      (node (ref "L102") (pin "2") (pinfunction "2_2") (pintype "passive"))
      (node (ref "Q102") (pin "G") (pinfunction "G_G") (pintype "passive"))
      (node (ref "R114") (pin "2") (pinfunction "2_2") (pintype "passive"))
      (node (ref "R116") (pin "1") (pinfunction "1_1") (pintype "passive"))
      (node (ref "R119") (pin "1") (pinfunction "1_1") (pintype "passive"))
      (node (ref "R120") (pin "1") (pinfunction "1_1") (pintype "passive"))
    )
    (net (code "18") (name "N5A_NEG") (class "Default")
      (node (ref "Q101") (pin "S") (pinfunction "S_S") (pintype "passive"))
      (node (ref "R121") (pin "1") (pinfunction "1_1") (pintype "passive"))
      (node (ref "R123") (pin "1") (pinfunction "1_1") (pintype "passive"))
      (node (ref "R125") (pin "1") (pinfunction "1_1") (pintype "passive"))
    )
    (net (code "19") (name "N5A_POS") (class "Default")
      (node (ref "Q102") (pin "S") (pinfunction "S_S") (pintype "passive"))
      (node (ref "R122") (pin "1") (pinfunction "1_1") (pintype "passive"))
      (node (ref "R124") (pin "1") (pinfunction "1_1") (pintype "passive"))
      (node (ref "R126") (pin "1") (pinfunction "1_1") (pintype "passive"))
    )
    (net (code "20") (name "Net-(C102-Pad1)") (class "Default")
      (node (ref "C102") (pin "1") (pinfunction "1_1") (pintype "passive"))
      (node (ref "R107") (pin "2") (pinfunction "2_2") (pintype "passive"))
      (node (ref "R108") (pin "1") (pinfunction "1_1") (pintype "passive"))
    )
    (net (code "21") (name "Net-(C104-Pad1)") (class "Default")
      (node (ref "C104") (pin "1") (pinfunction "1_1") (pintype "passive"))
      (node (ref "R109") (pin "2") (pinfunction "2_2") (pintype "passive"))
      (node (ref "R110") (pin "1") (pinfunction "1_1") (pintype "passive"))
    )
    (net (code "22") (name "Net-(C106-Pad1)") (class "Default")
      (node (ref "C106") (pin "1") (pinfunction "1_1") (pintype "passive"))
      (node (ref "R111") (pin "2") (pinfunction "2_2") (pintype "passive"))
    )
    (net (code "23") (name "Net-(C107-Pad1)") (class "Default")
      (node (ref "C107") (pin "1") (pinfunction "1_1") (pintype "passive"))
      (node (ref "R112") (pin "2") (pinfunction "2_2") (pintype "passive"))
    )
    (net (code "24") (name "Net-(C109-Pad1)") (class "Default")
      (node (ref "C109") (pin "1") (pinfunction "1_1") (pintype "passive"))
      (node (ref "R115") (pin "2") (pinfunction "2_2") (pintype "passive"))
    )
    (net (code "25") (name "Net-(C110-Pad1)") (class "Default")
      (node (ref "C110") (pin "1") (pinfunction "1_1") (pintype "passive"))
      (node (ref "R116") (pin "2") (pinfunction "2_2") (pintype "passive"))
    )
    (net (code "26") (name "Net-(C111-Pad1)") (class "Default")
      (node (ref "C111") (pin "1") (pinfunction "1_1") (pintype "passive"))
      (node (ref "R117") (pin "2") (pinfunction "2_2") (pintype "passive"))
      (node (ref "R118") (pin "2") (pinfunction "2_2") (pintype "passive"))
    )
    (net (code "27") (name "Net-(C112-Pad1)") (class "Default")
      (node (ref "C112") (pin "1") (pinfunction "1_1") (pintype "passive"))
      (node (ref "R119") (pin "2") (pinfunction "2_2") (pintype "passive"))
      (node (ref "R120") (pin "2") (pinfunction "2_2") (pintype "passive"))
    )
    (net (code "28") (name "Net-(C116-Pad2)") (class "Default")
      (node (ref "C116") (pin "2") (pinfunction "2_2") (pintype "passive"))
      (node (ref "R127") (pin "1") (pinfunction "1_1") (pintype "passive"))
    )
    (net (code "29") (name "Net-(C207-Pad1)") (class "Default")
      (node (ref "C207") (pin "1") (pinfunction "1_1") (pintype "passive"))
      (node (ref "R214") (pin "1") (pinfunction "1_1") (pintype "passive"))
    )
    (net (code "30") (name "Net-(C209-Pad1)") (class "Default")
      (node (ref "C209") (pin "1") (pinfunction "1_1") (pintype "passive"))
      (node (ref "R216") (pin "2") (pinfunction "2_2") (pintype "passive"))
    )
    (net (code "31") (name "Net-(C301-Pad+)") (class "Default")
      (node (ref "C301") (pin "+") (pinfunction "+_+") (pintype "passive"))
      (node (ref "L301") (pin "1") (pinfunction "1_1") (pintype "passive"))
      (node (ref "R301") (pin "2") (pinfunction "2_2") (pintype "passive"))
      (node (ref "R302") (pin "1") (pinfunction "1_1") (pintype "passive"))
      (node (ref "R303") (pin "1") (pinfunction "1_1") (pintype "passive"))
    )
    (net (code "32") (name "Net-(C302-Pad1)") (class "Default")
      (node (ref "C302") (pin "1") (pinfunction "1_1") (pintype "passive"))
      (node (ref "C303") (pin "1") (pinfunction "1_1") (pintype "passive"))
      (node (ref "L301") (pin "2") (pinfunction "2_2") (pintype "passive"))
      (node (ref "L302") (pin "1") (pinfunction "1_1") (pintype "passive"))
      (node (ref "R304") (pin "1") (pinfunction "1_1") (pintype "passive"))
    )
    (net (code "33") (name "Net-(D301-PadC)") (class "Default")
      (node (ref "D301") (pin "C") (pinfunction "C_C") (pintype "passive"))
      (node (ref "F301") (pin "2") (pinfunction "2_2") (pintype "passive"))
      (node (ref "R301") (pin "1") (pinfunction "1_1") (pintype "passive"))
    )
    (net (code "34") (name "Net-(F301-Pad1)") (class "Default")
      (node (ref "F301") (pin "1") (pinfunction "1_1") (pintype "passive"))
      (node (ref "JP301") (pin "2") (pinfunction "2_2") (pintype "passive"))
    )
    (net (code "35") (name "Net-(IC201A-I)") (class "Default")
      (node (ref "IC201") (pin "2") (pinfunction "I_2") (pintype "input"))
      (node (ref "J202") (pin "C") (pinfunction "1_C") (pintype "passive"))
      (node (ref "R204") (pin "1") (pinfunction "1_1") (pintype "passive"))
    )
    (net (code "36") (name "Net-(IC201A-O)") (class "Default")
      (node (ref "IC201") (pin "4") (pinfunction "O_4") (pintype "output"))
      (node (ref "Q201") (pin "1") (pinfunction "G_1") (pintype "passive"))
    )
    (net (code "37") (name "Net-(IC202A-+IN)") (class "Default")
      (node (ref "C208") (pin "1") (pinfunction "1_1") (pintype "passive"))
      (node (ref "IC202") (pin "3") (pinfunction "+IN_3") (pintype "input"))
      (node (ref "R209") (pin "2") (pinfunction "2_2") (pintype "passive"))
      (node (ref "R211") (pin "1") (pinfunction "1_1") (pintype "passive"))
    )
    (net (code "38") (name "Net-(IC202A--IN)") (class "Default")
      (node (ref "C209") (pin "2") (pinfunction "2_2") (pintype "passive"))
      (node (ref "IC202") (pin "2") (pinfunction "-IN_2") (pintype "input"))
      (node (ref "R212") (pin "2") (pinfunction "2_2") (pintype "passive"))
      (node (ref "R214") (pin "2") (pinfunction "2_2") (pintype "passive"))
      (node (ref "R219") (pin "1") (pinfunction "1_1") (pintype "passive"))
    )
    (net (code "39") (name "Net-(IC202A-OUT)") (class "Default")
      (node (ref "IC202") (pin "1") (pinfunction "OUT_1") (pintype "output"))
      (node (ref "R216") (pin "1") (pinfunction "1_1") (pintype "passive"))
      (node (ref "R217") (pin "1") (pinfunction "1_1") (pintype "passive"))
    )
    (net (code "40") (name "Net-(IC202B-+IN)") (class "Default")
      (node (ref "IC202") (pin "5") (pinfunction "+IN_5") (pintype "input"))
      (node (ref "R203") (pin "2") (pinfunction "2_2") (pintype "passive"))
      (node (ref "R206") (pin "1") (pinfunction "1_1") (pintype "passive"))
    )
    (net (code "41") (name "Net-(IC202B--IN)") (class "Default")
      (node (ref "IC202") (pin "6") (pinfunction "-IN_6") (pintype "input"))
      (node (ref "JP202") (pin "1") (pinfunction "1_1") (pintype "passive"))
      (node (ref "R202") (pin "2") (pinfunction "2_2") (pintype "passive"))
      (node (ref "R205") (pin "1") (pinfunction "1_1") (pintype "passive"))
    )
    (net (code "42") (name "Net-(IC202B-OUT)") (class "Default")
      (node (ref "IC202") (pin "7") (pinfunction "OUT_7") (pintype "output"))
      (node (ref "JP202") (pin "2") (pinfunction "2_2") (pintype "passive"))
      (node (ref "R205") (pin "2") (pinfunction "2_2") (pintype "passive"))
      (node (ref "R207") (pin "1") (pinfunction "1_1") (pintype "passive"))
    )
    (net (code "43") (name "Net-(IC202C-+IN)") (class "Default")
      (node (ref "C201") (pin "1") (pinfunction "1_1") (pintype "passive"))
      (node (ref "IC202") (pin "10") (pinfunction "+IN_10") (pintype "input"))
      (node (ref "R201") (pin "2") (pinfunction "S_2") (pintype "passive"))
    )
    (net (code "44") (name "Net-(IC202C--IN)") (class "Default")
      (node (ref "IC202") (pin "8") (pinfunction "OUT_8") (pintype "output"))
      (node (ref "IC202") (pin "9") (pinfunction "-IN_9") (pintype "input"))
      (node (ref "R206") (pin "2") (pinfunction "2_2") (pintype "passive"))
    )
    (net (code "45") (name "Net-(IC202D-+IN)") (class "Default")
      (node (ref "IC202") (pin "12") (pinfunction "+IN_12") (pintype "input"))
      (node (ref "Q201") (pin "3") (pinfunction "D_3") (pintype "passive"))
      (node (ref "R207") (pin "2") (pinfunction "2_2") (pintype "passive"))
    )
    (net (code "46") (name "Net-(IC202D--IN)") (class "Default")
      (node (ref "IC202") (pin "13") (pinfunction "-IN_13") (pintype "input"))
      (node (ref "IC202") (pin "14") (pinfunction "OUT_14") (pintype "output"))
      (node (ref "R209") (pin "1") (pinfunction "1_1") (pintype "passive"))
    )
    (net (code "47") (name "Net-(IC301-PadIN)") (class "Default")
      (node (ref "IC301") (pin "IN") (pinfunction "IN_IN") (pintype "input"))
      (node (ref "R302") (pin "2") (pinfunction "2_2") (pintype "passive"))
    )
    (net (code "48") (name "Net-(IC302-PadIN)") (class "Default")
      (node (ref "IC302") (pin "IN") (pinfunction "IN_IN") (pintype "input"))
      (node (ref "R303") (pin "2") (pinfunction "2_2") (pintype "passive"))
    )
    (net (code "49") (name "Net-(J101-1)") (class "Default")
      (node (ref "C101") (pin "1") (pinfunction "1_1") (pintype "passive"))
      (node (ref "J101") (pin "C") (pinfunction "1_C") (pintype "passive"))
    )
    (net (code "50") (name "Net-(J102-1)") (class "Default")
      (node (ref "C117") (pin "2") (pinfunction "2_2") (pintype "passive"))
      (node (ref "J102") (pin "C") (pinfunction "1_C") (pintype "passive"))
    )
    (net (code "51") (name "Net-(J201-1)") (class "Default")
      (node (ref "J201") (pin "C") (pinfunction "1_C") (pintype "passive"))
      (node (ref "JP201") (pin "2") (pinfunction "2_2") (pintype "passive"))
      (node (ref "R202") (pin "1") (pinfunction "1_1") (pintype "passive"))
    )
    (net (code "52") (name "Net-(J201-GND1-PadG1)") (class "Default")
      (node (ref "J201") (pin "G1") (pinfunction "GND1_G1") (pintype "power_in"))
      (node (ref "J201") (pin "G2") (pinfunction "GND1_G2") (pintype "power_in"))
      (node (ref "J201") (pin "G3") (pinfunction "GND1_G3") (pintype "power_in"))
      (node (ref "J201") (pin "G4") (pinfunction "GND1_G4") (pintype "power_in"))
      (node (ref "JP201") (pin "1") (pinfunction "1_1") (pintype "passive"))
      (node (ref "R203") (pin "1") (pinfunction "1_1") (pintype "passive"))
    )
    (net (code "53") (name "Net-(R217-Pad2)") (class "Default")
      (node (ref "R217") (pin "2") (pinfunction "2_2") (pintype "passive"))
      (node (ref "R218") (pin "1") (pinfunction "1_1") (pintype "passive"))
      (node (ref "T201") (pin "B") (pinfunction "B_B") (pintype "passive"))
      (node (ref "T202") (pin "B") (pinfunction "B_B") (pintype "passive"))
    )
    (net (code "54") (name "Net-(T101-F2)") (class "Default")
      (node (ref "T101") (pin "1") (pinfunction "S1_1") (pintype "passive"))
      (node (ref "T101") (pin "11") (pinfunction "F2_11") (pintype "passive"))
    )
    (net (code "55") (name "Net-(T101-F4)") (class "Default")
      (node (ref "T101") (pin "3") (pinfunction "S3_3") (pintype "passive"))
      (node (ref "T101") (pin "9") (pinfunction "F4_9") (pintype "passive"))
    )
    (net (code "56") (name "Net-(T101-F6)") (class "Default")
      (node (ref "T101") (pin "5") (pinfunction "S5_5") (pintype "passive"))
      (node (ref "T101") (pin "7") (pinfunction "F6_7") (pintype "passive"))
    )
    (net (code "57") (name "Net-(T101-S6)") (class "Default")
      (node (ref "C101") (pin "2") (pinfunction "2_2") (pintype "passive"))
      (node (ref "T101") (pin "6") (pinfunction "S6_6") (pintype "passive"))
    )
    (net (code "58") (name "Net-(T102-F2)") (class "Default")
      (node (ref "T102") (pin "1") (pinfunction "S1_1") (pintype "passive"))
      (node (ref "T102") (pin "11") (pinfunction "F2_11") (pintype "passive"))
    )
    (net (code "59") (name "Net-(T102-F3)") (class "Default")
      (node (ref "T102") (pin "10") (pinfunction "F3_10") (pintype "passive"))
      (node (ref "T102") (pin "2") (pinfunction "S2_2") (pintype "passive"))
    )
    (net (code "60") (name "Net-(T102-F4)") (class "Default")
      (node (ref "T102") (pin "3") (pinfunction "S3_3") (pintype "passive"))
      (node (ref "T102") (pin "9") (pinfunction "F4_9") (pintype "passive"))
    )
    (net (code "61") (name "Net-(T102-F6)") (class "Default")
      (node (ref "C115") (pin "1") (pinfunction "1_1") (pintype "passive"))
      (node (ref "C116") (pin "1") (pinfunction "1_1") (pintype "passive"))
      (node (ref "L103") (pin "2") (pinfunction "2_2") (pintype "passive"))
      (node (ref "T102") (pin "5") (pinfunction "S5_5") (pintype "passive"))
      (node (ref "T102") (pin "7") (pinfunction "F6_7") (pintype "passive"))
    )
    (net (code "62") (name "Net-(T102-S4)") (class "Default")
      (node (ref "C117") (pin "1") (pinfunction "1_1") (pintype "passive"))
      (node (ref "T102") (pin "4") (pinfunction "S4_4") (pintype "passive"))
    )
    (net (code "63") (name "VB") (class "Default")
      (node (ref "C304") (pin "1") (pinfunction "1_1") (pintype "passive"))
      (node (ref "L302") (pin "2") (pinfunction "2_2") (pintype "passive"))
      (node (ref "R304") (pin "2") (pinfunction "2_2") (pintype "passive"))
    )
    (net (code "64") (name "unconnected-(C108-Pad1)") (class "Default")
      (node (ref "C108") (pin "1") (pinfunction "1_1") (pintype "passive"))
    )
    (net (code "65") (name "unconnected-(C108-Pad2)") (class "Default")
      (node (ref "C108") (pin "2") (pinfunction "2_2") (pintype "passive"))
    )
    (net (code "66") (name "unconnected-(C202-Pad1)") (class "Default")
      (node (ref "C202") (pin "1") (pinfunction "1_1") (pintype "passive"))
    )
    (net (code "67") (name "unconnected-(C202-Pad2)") (class "Default")
      (node (ref "C202") (pin "2") (pinfunction "2_2") (pintype "passive"))
    )
    (net (code "68") (name "unconnected-(C203-Pad1)") (class "Default")
      (node (ref "C203") (pin "1") (pinfunction "1_1") (pintype "passive"))
    )
    (net (code "69") (name "unconnected-(C203-Pad2)") (class "Default")
      (node (ref "C203") (pin "2") (pinfunction "2_2") (pintype "passive"))
    )
    (net (code "70") (name "unconnected-(C204-Pad1)") (class "Default")
      (node (ref "C204") (pin "1") (pinfunction "1_1") (pintype "passive"))
    )
    (net (code "71") (name "unconnected-(C204-Pad2)") (class "Default")
      (node (ref "C204") (pin "2") (pinfunction "2_2") (pintype "passive"))
    )
    (net (code "72") (name "unconnected-(C205-Pad1)") (class "Default")
      (node (ref "C205") (pin "1") (pinfunction "1_1") (pintype "passive"))
    )
    (net (code "73") (name "unconnected-(C205-Pad2)") (class "Default")
      (node (ref "C205") (pin "2") (pinfunction "2_2") (pintype "passive"))
    )
    (net (code "74") (name "unconnected-(C206-Pad1)") (class "Default")
      (node (ref "C206") (pin "1") (pinfunction "1_1") (pintype "passive"))
    )
    (net (code "75") (name "unconnected-(C206-Pad2)") (class "Default")
      (node (ref "C206") (pin "2") (pinfunction "2_2") (pintype "passive"))
    )
    (net (code "76") (name "unconnected-(L103-Pad1)") (class "Default")
      (node (ref "L103") (pin "1") (pinfunction "1_1") (pintype "passive"))
    )
    (net (code "77") (name "unconnected-(R208-Pad1)") (class "Default")
      (node (ref "R208") (pin "1") (pinfunction "1_1") (pintype "passive"))
    )
    (net (code "78") (name "unconnected-(R208-Pad2)") (class "Default")
      (node (ref "R208") (pin "2") (pinfunction "2_2") (pintype "passive"))
    )
    (net (code "79") (name "unconnected-(R210-Pad1)") (class "Default")
      (node (ref "R210") (pin "1") (pinfunction "1_1") (pintype "passive"))
    )
    (net (code "80") (name "unconnected-(R210-Pad2)") (class "Default")
      (node (ref "R210") (pin "2") (pinfunction "2_2") (pintype "passive"))
    )
    (net (code "81") (name "unconnected-(R213-Pad1)") (class "Default")
      (node (ref "R213") (pin "1") (pinfunction "1_1") (pintype "passive"))
    )
    (net (code "82") (name "unconnected-(R213-Pad2)") (class "Default")
      (node (ref "R213") (pin "2") (pinfunction "2_2") (pintype "passive"))
    )
    (net (code "83") (name "unconnected-(R215-Pad1)") (class "Default")
      (node (ref "R215") (pin "1") (pinfunction "1_1") (pintype "passive"))
    )
    (net (code "84") (name "unconnected-(R215-Pad2)") (class "Default")
      (node (ref "R215") (pin "2") (pinfunction "2_2") (pintype "passive"))
    )
    (net (code "85") (name "unconnected-(X101-P$1-PadP1)") (class "Default")
      (node (ref "X101") (pin "P1") (pinfunction "P$1_P1") (pintype "bidirectional"))
    )
    (net (code "86") (name "unconnected-(X101-P$2-PadP2)") (class "Default")
      (node (ref "X101") (pin "P2") (pinfunction "P$2_P2") (pintype "bidirectional"))
    )
  )
)
